# xbowtie1.net
KiCad netlist of a schematic drawn in Altium Designer
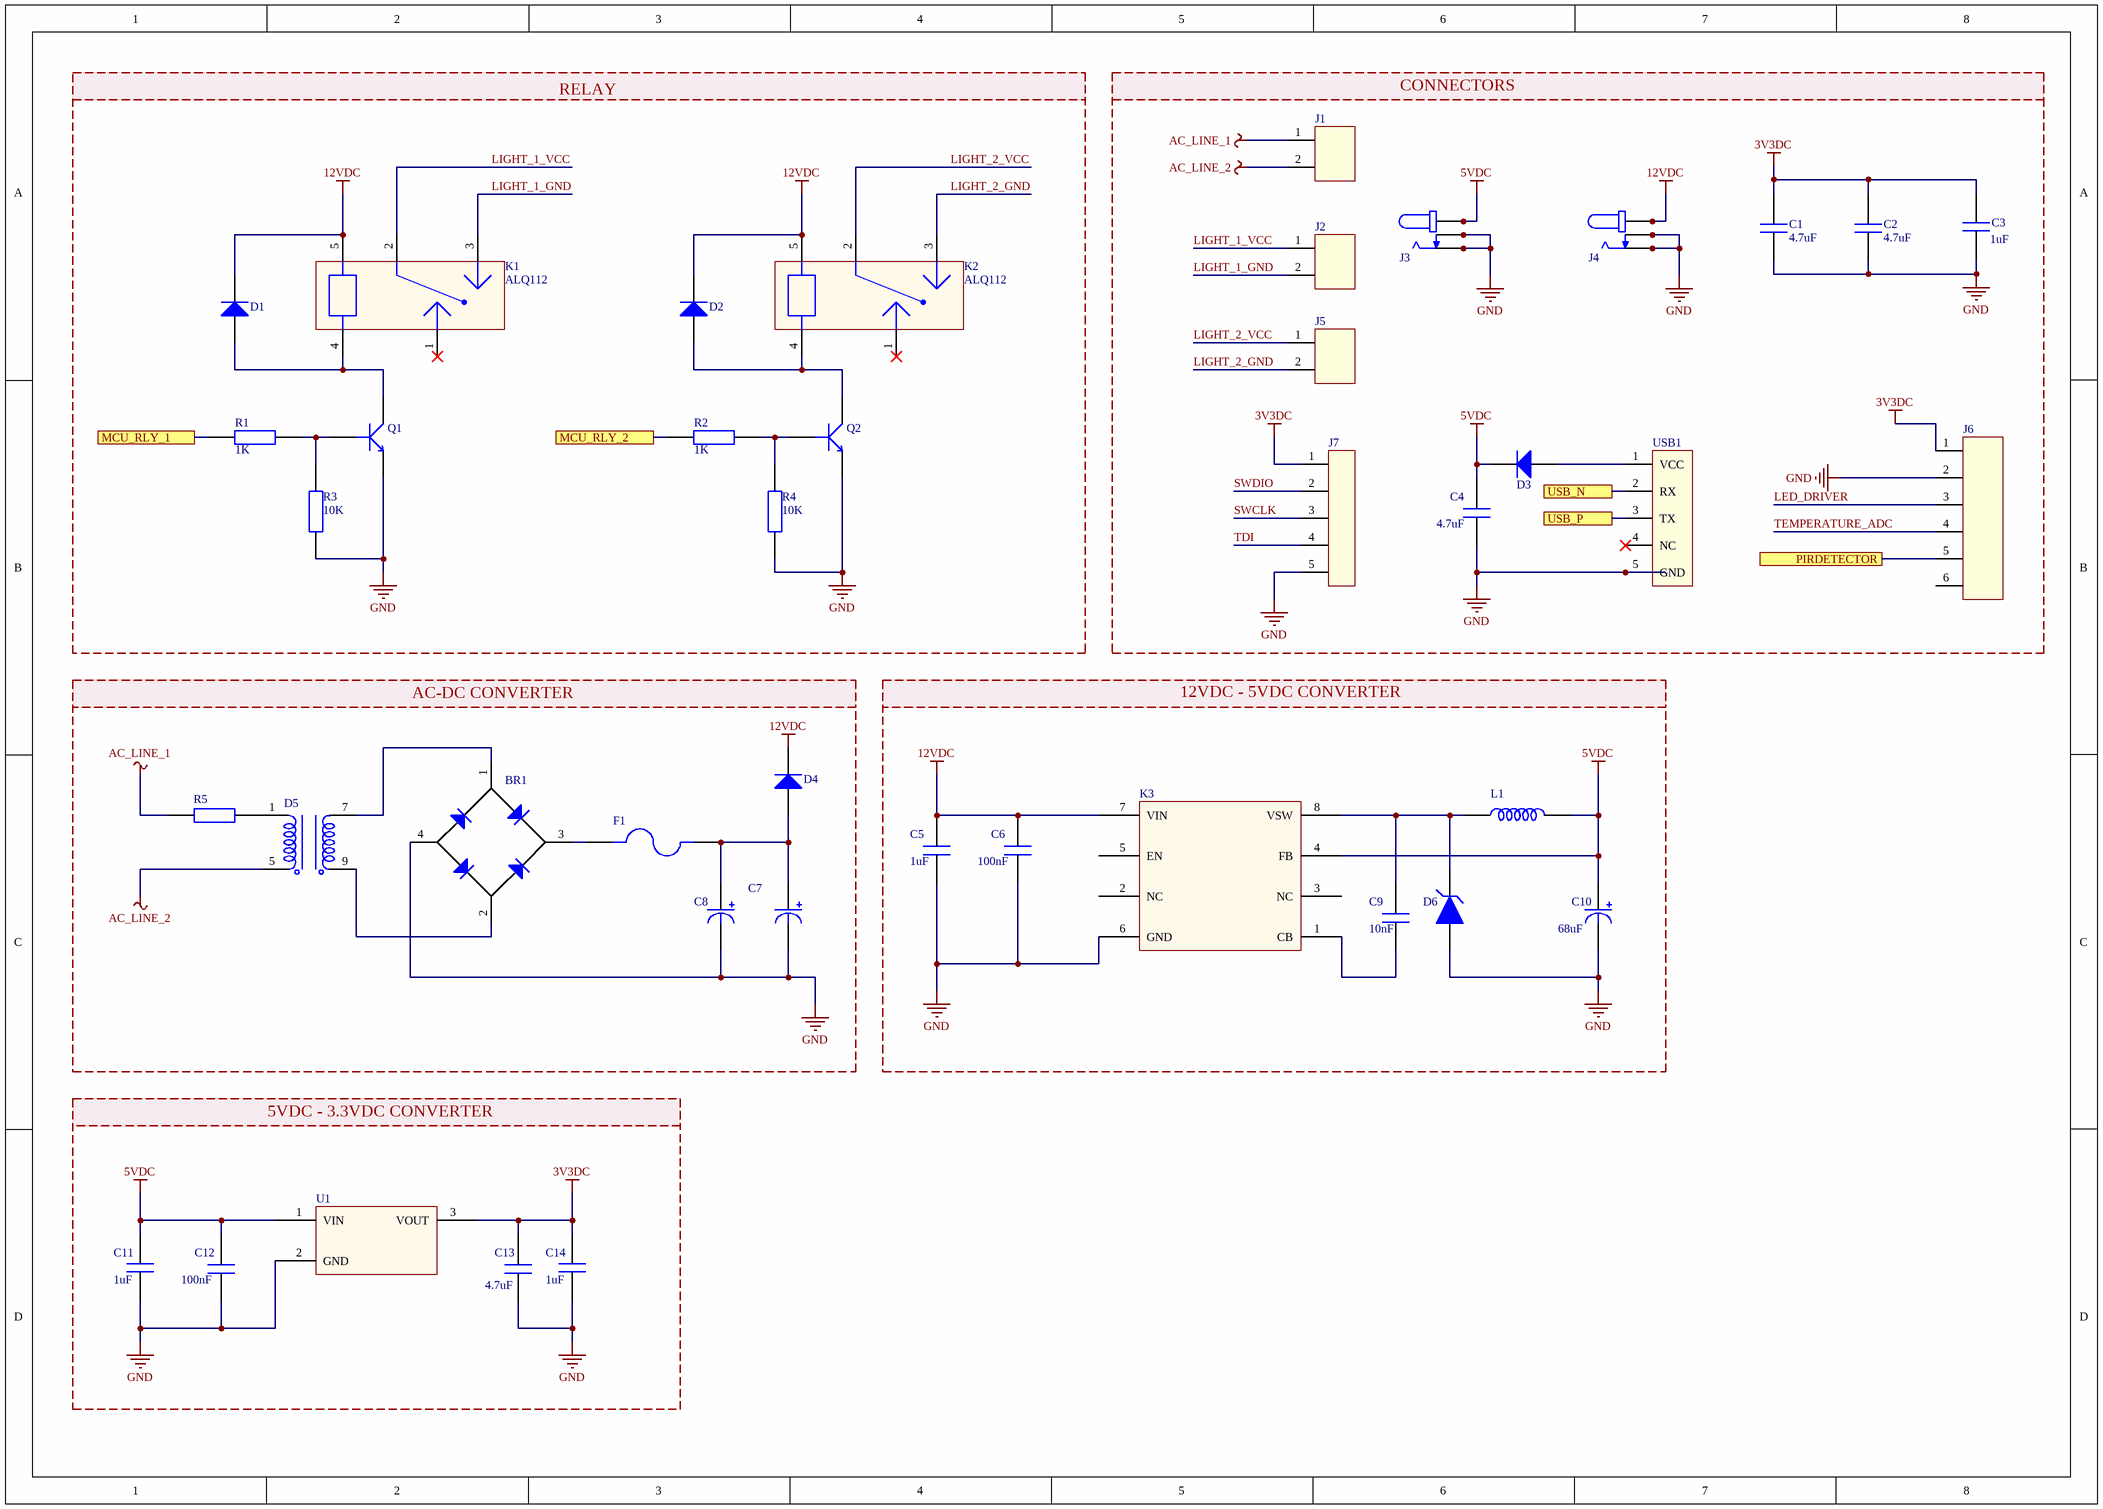
[diagram p0: xbowtie1.SchDoc]

(export (version "E")
  (design (tool "Eeschema 10.0.6"))
  (components
    (comp (ref "BR1") (value "DB105STR") (footprint "DB105STR") (libsource (lib "xbowtie") (part "DB105STR")))
    (comp (ref "C1")
      (value "4.7uF")
      (footprint "CAP_CER 0805")
      (description "CAP CER 4.7uF 0805")
      (fields
        (field (name "MANUFACTURER") "Samsung")
        (field (name "MANUFACTURER PART NUMBER") "CL21A475KBQNNNE")
      )
      (libsource (lib "xbowtie") (part "CAP CER 4.7uF 0805"))
    )
    (comp (ref "C2")
      (value "4.7uF")
      (footprint "CAP_CER 0805")
      (description "CAP CER 4.7uF 0805")
      (fields
        (field (name "MANUFACTURER") "Samsung")
        (field (name "MANUFACTURER PART NUMBER") "CL21A475KBQNNNE")
      )
      (libsource (lib "xbowtie") (part "CAP CER 4.7uF 0805"))
    )
    (comp (ref "C3")
      (value "CAP CER 1uF 0805")
      (footprint "CAP_CER 0805")
      (description "CAP CER 1uF %10 0805")
      (fields
        (field (name "MANUFACTURER") "Samsung")
        (field (name "MANUFACTURER PART NUMBER") "CL21B105KBFNNNE")
        (field (name "CAPACITANCE") "1uF")
      )
      (libsource (lib "xbowtie") (part "CAP CER 1uF 0805"))
    )
    (comp (ref "C4")
      (value "4.7uF")
      (footprint "CAP_CER 0805")
      (description "CAP CER 4.7uF 0805")
      (fields
        (field (name "MANUFACTURER") "Samsung")
        (field (name "MANUFACTURER PART NUMBER") "CL21A475KBQNNNE")
      )
      (libsource (lib "xbowtie") (part "CAP CER 4.7uF 0805"))
    )
    (comp (ref "C5")
      (value "1uF")
      (footprint "CAP_CER 0805")
      (description "CAP CER 1uF %10 0805")
      (fields
        (field (name "MANUFACTURER") "Samsung")
        (field (name "MANUFACTURER PART NUMBER") "CL21B105KBFNNNE")
      )
      (libsource (lib "") (part "CAP CER 1uF 0805_1"))
    )
    (comp (ref "C6")
      (value "100nF")
      (footprint "CAP_CER 0805")
      (libsource (lib "xbowtie") (part "CAP CER 100nF 0805"))
    )
    (comp (ref "C7")
      (value "ESH477M050AH4AA")
      (footprint "ESH477")
      (description "Cap, 470UF, 50V, Alu Elec, Radial")
      (fields (field (name "MANUFACTURER") "KEMET"))
      (libsource (lib "xbowtie") (part "ESH477M050AH4AA"))
    )
    (comp (ref "C8")
      (value "ESH477M050AH4AA")
      (footprint "ESH477")
      (description "Cap, 470UF, 50V, Alu Elec, Radial")
      (fields (field (name "MANUFACTURER") "KEMET"))
      (libsource (lib "xbowtie") (part "ESH477M050AH4AA"))
    )
    (comp (ref "C9")
      (value "10nF")
      (footprint "cap_0603")
      (fields
        (field (name "MANUFACTURER") "Walsin Technologies")
        (field (name "MANUFACTURER PART NUMBER") "0603B103K160CT")
      )
      (libsource (lib "xbowtie") (part "CAP CER 10nF 0603"))
    )
    (comp (ref "C10")
      (value "68uF")
      (footprint "CAP ALU 68 uF")
      (description "Cap Aluminum Lytic 68uF 35V 20%( 6.3 X 7.7mm) SMD 0.34 Ohm 280mA 2000h 105C T/R")
      (fields
        (field (name "MANUFACTURER") "KEMET")
        (field (name "MANUFACTURER PART NUMBER") "EEV686M035A9HAA")
      )
      (libsource (lib "xbowtie") (part "CAP ALU 68 uF"))
    )
    (comp (ref "C11")
      (value "CAP CER 1uF 0805")
      (footprint "CAP_CER 0805")
      (description "CAP CER 1uF %10 0805")
      (fields
        (field (name "MANUFACTURER") "Samsung")
        (field (name "MANUFACTURER PART NUMBER") "CL21B105KBFNNNE")
        (field (name "CAPACITANCE") "1uF")
      )
      (libsource (lib "xbowtie") (part "CAP CER 1uF 0805"))
    )
    (comp (ref "C12")
      (value "100nF")
      (footprint "CAP_CER 0805")
      (libsource (lib "xbowtie") (part "CAP CER 100nF 0805"))
    )
    (comp (ref "C13")
      (value "CAP CER 4.7uF 0805")
      (footprint "CAP_CER 0805")
      (fields
        (field (name "MANUFACTURER") "Samsung")
        (field (name "MANUFACTURER PART NUMBER") "CL21A475KBQNNNE")
        (field (name "TOLERANCE") "10%")
        (field (name "CAPACITANCE") "4.7uF")
      )
      (libsource (lib "xbowtie") (part "CAP CER 4.7uF 0805"))
    )
    (comp (ref "C14")
      (value "CAP CER 1uF 0805")
      (footprint "CAP_CER 0805")
      (description "CAP CER 1uF %10 0805")
      (fields
        (field (name "MANUFACTURER") "Samsung")
        (field (name "MANUFACTURER PART NUMBER") "CL21B105KBFNNNE")
        (field (name "CAPACITANCE") "1uF")
      )
      (libsource (lib "xbowtie") (part "CAP CER 1uF 0805"))
    )
    (comp (ref "D1")
      (value "1N4148WS")
      (footprint "1N4148WS")
      (description "Diode Ultra Fast Recovery Rectifier 75V 0.15A 2-Pin SOD-323F T/R")
      (fields (field (name "MANUFACTURER") "ON Semiconductor / Fairchild"))
      (libsource (lib "xbowtie") (part "1N4148WS"))
    )
    (comp (ref "D2")
      (value "1N4148WS")
      (footprint "1N4148WS")
      (description "Diode Ultra Fast Recovery Rectifier 75V 0.15A 2-Pin SOD-323F T/R")
      (fields (field (name "MANUFACTURER") "ON Semiconductor / Fairchild"))
      (libsource (lib "xbowtie") (part "1N4148WS"))
    )
    (comp (ref "D3")
      (value "1N4148WS")
      (footprint "1N4148WS")
      (description "Diode Ultra Fast Recovery Rectifier 75V 0.15A 2-Pin SOD-323F T/R")
      (fields (field (name "MANUFACTURER") "ON Semiconductor / Fairchild"))
      (libsource (lib "xbowtie") (part "1N4148WS"))
    )
    (comp (ref "D4")
      (value "1N4148WS")
      (footprint "1N4148WS")
      (description "Diode Ultra Fast Recovery Rectifier 75V 0.15A 2-Pin SOD-323F T/R")
      (fields (field (name "MANUFACTURER") "ON Semiconductor / Fairchild"))
      (libsource (lib "xbowtie") (part "1N4148WS"))
    )
    (comp (ref "D5")
      (value "BV302S12010_ZU")
      (footprint "BV302S")
      (libsource (lib "xbowtie") (part "BV302S12010_ZU"))
    )
    (comp (ref "D6")
      (value "1SMB5919BT3G")
      (footprint "1SMB5919BT3G")
      (description "Vz=5.6V 5.32V~5.88V Izt=66.9mA")
      (fields (field (name "MANUFACTURER") "ON Semiconductor"))
      (libsource (lib "xbowtie") (part "1SMB5919BT3G"))
    )
    (comp (ref "F1")
      (value "FUSE 3413.0216.22")
      (footprint "FUSE 3413.0216.22")
      (description "Fuse Chip Fast Acting 1A 32V SMD Solder Pad 1206 Glass T/R VDE/cULus")
      (fields
        (field (name "MANUFACTURER") "Schurter")
        (field (name "MANUFACTURER PART NUMBER") "3413.0216.22")
        (field (name "DESIGNED BY") "Nisanur")
      )
      (libsource (lib "xbowtie") (part "FUSE 3413.0216.22"))
    )
    (comp (ref "J1")
      (value "TBP01R1-508-02BE")
      (footprint "TBP01R1-508")
      (description "2~24 Poles, Pluggable, Receptacle, Horizontal, 5.08 Pitch, Terminal Block Connector")
      (fields (field (name "MANUFACTURER") "CUI Devices"))
      (libsource (lib "xbowtie") (part "TBP01R1-508-02BE"))
    )
    (comp (ref "J2")
      (value "TBP01R1-508-02BE")
      (footprint "TBP01R1-508")
      (description "2~24 Poles, Pluggable, Receptacle, Horizontal, 5.08 Pitch, Terminal Block Connector")
      (fields (field (name "MANUFACTURER") "CUI Devices"))
      (libsource (lib "xbowtie") (part "TBP01R1-508-02BE"))
    )
    (comp (ref "J3")
      (value "PJ-037AH-SMT-TR")
      (footprint "JACK")
      (description "2.0 x 6.3 mm, 5.0 A, Horizontal, Surface Mount (SMT), Dc Power Jack Connector")
      (fields (field (name "MANUFACTURER") "CUI"))
      (libsource (lib "xbowtie") (part "PJ-037AH-SMT-TR"))
    )
    (comp (ref "J4")
      (value "PJ-037AH-SMT-TR")
      (footprint "JACK")
      (description "2.0 x 6.3 mm, 5.0 A, Horizontal, Surface Mount (SMT), Dc Power Jack Connector")
      (fields (field (name "MANUFACTURER") "CUI"))
      (libsource (lib "xbowtie") (part "PJ-037AH-SMT-TR"))
    )
    (comp (ref "J5")
      (value "TBP01R1-508-02BE")
      (footprint "TBP01R1-508")
      (description "2~24 Poles, Pluggable, Receptacle, Horizontal, 5.08 Pitch, Terminal Block Connector")
      (fields (field (name "MANUFACTURER") "CUI Devices"))
      (libsource (lib "xbowtie") (part "TBP01R1-508-02BE"))
    )
    (comp (ref "J6")
      (value "64800611622")
      (footprint "64800611622")
      (description "1.50 mm, 6 pin connector")
      (fields (field (name "MANUFACTURER") "Wurth Electronics"))
      (libsource (lib "xbowtie") (part "64800611622_conn_6pin"))
    )
    (comp (ref "J7")
      (value "SMH-105-02-LS")
      (footprint "5 PIN CONNECTOR")
      (description "Samtec - SMH-105-02-L-S - Receptacle, 2.54MM, Tht, R/a, 5WAY")
      (fields
        (field (name "MANUFACTURER") "Samtec")
        (field (name "MANUFACTURER PART NUMBER") "SMH-105-02-L-S")
      )
      (libsource (lib "xbowtie") (part "SMH-105-02-LS"))
    )
    (comp (ref "K1")
      (value "ALQ112")
      (footprint "ALQ112")
      (description "Electromechanical Relay 12VDC 360Ohm 10(NO)/3(NC)A SPDT (( 20mm 10mm 16mm)) THT Power Relay")
      (fields (field (name "MANUFACTURER") "Panasonic"))
      (libsource (lib "xbowtie") (part "ALQ112"))
    )
    (comp (ref "K2")
      (value "ALQ112")
      (footprint "ALQ112")
      (description "Electromechanical Relay 12VDC 360Ohm 10(NO)/3(NC)A SPDT (( 20mm 10mm 16mm)) THT Power Relay")
      (fields (field (name "MANUFACTURER") "Panasonic"))
      (libsource (lib "xbowtie") (part "ALQ112"))
    )
    (comp (ref "K3")
      (value "LM2675MX-12/NOPB")
      (footprint "LM2675MX-12/NOPB")
      (description "SIMPLE SWITCHER® 6.5V to 40V, 1A Low Component Count Step-Down Regulator 8-SOIC -40 to 125")
      (fields (field (name "MANUFACTURER") "TI National Semiconductor"))
      (libsource (lib "xbowtie") (part "LM2675MX-12/NOPB"))
    )
    (comp (ref "L1")
      (value "78438335470")
      (footprint "IND_1212")
      (description "Power Inductor, Aec-Q200, 47Uh, 0.39A Rohs Compliant: Yes ¦Wurth Elektronik 78438335470")
      (fields (field (name "MANUFACTURER") "Wurth Electronics") (field (name "TOLERANCE") "30%"))
      (libsource (lib "xbowtie") (part "IND 47 uH"))
    )
    (comp (ref "Q1")
      (value "MMBT3904-7-F")
      (footprint "MMBT3904-7-F")
      (description "Transistor General Purpose BJT NPN 40 Volt 0.2A Automotive 3-Pin SOT-23")
      (fields (field (name "MANUFACTURER") "Diodes Zetex"))
      (libsource (lib "xbowtie") (part "MMBT3904-7-F"))
    )
    (comp (ref "Q2")
      (value "MMBT3904-7-F")
      (footprint "MMBT3904-7-F")
      (description "Transistor General Purpose BJT NPN 40 Volt 0.2A Automotive 3-Pin SOT-23")
      (fields (field (name "MANUFACTURER") "Diodes Zetex"))
      (libsource (lib "xbowtie") (part "MMBT3904-7-F"))
    )
    (comp (ref "R1") (value "1K") (footprint "RES_0603") (libsource (lib "xbowtie") (part "RES 1K OHM 0603")))
    (comp (ref "R2") (value "1K") (footprint "RES_0603") (libsource (lib "xbowtie") (part "RES 1K OHM 0603")))
    (comp (ref "R3")
      (value "10K")
      (footprint "RES_0603")
      (description "Res Thin Film 0603 10K Ohm 0.1% 1/10W ±25ppm/°C Molded SMD SMD Punched Carrier T/R")
      (fields
        (field (name "MANUFACTURER") "Panasonic")
        (field (name "MANUFACTURER PART NUMBER") "ERA-3AEB103V")
      )
      (libsource (lib "xbowtie") (part "RES 10K OHM 0603"))
    )
    (comp (ref "R4")
      (value "10K")
      (footprint "RES_0603")
      (description "Res Thin Film 0603 10K Ohm 0.1% 1/10W ±25ppm/°C Molded SMD SMD Punched Carrier T/R")
      (fields
        (field (name "MANUFACTURER") "Panasonic")
        (field (name "MANUFACTURER PART NUMBER") "ERA-3AEB103V")
      )
      (libsource (lib "xbowtie") (part "RES 10K OHM 0603"))
    )
    (comp (ref "R5") (value "5WD27") (footprint "5WD27") (libsource (lib "xbowtie") (part "5WD27")))
    (comp (ref "U1")
      (value "AP7361-33E-13")
      (footprint "AP7361-33E-13")
      (description "AP7361 Series 3.3 V 1 A Low SMT Dropout Fixed-Mode Regulator - SOT-223")
      (fields (field (name "MANUFACTURER") "Diodes"))
      (libsource (lib "xbowtie") (part "AP7361-33E-13"))
    )
    (comp (ref "USB1")
      (value "10118192-0001LF")
      (footprint "MICRO_B_USB")
      (description "CONN USB MICRO B RECPT SMT R/A")
      (fields (field (name "MANUFACTURER") "Amphenol ICC / FCI"))
      (libsource (lib "xbowtie") (part "MİCRO B USB Connector"))
    )
  )
  (nets
    (net (code "1") (name "/LED_DRIVER") (class "Default")
      (node (ref "J6") (pin "3") (pinfunction "TX_3") (pintype "passive"))
    )
    (net (code "2") (name "/LIGHT_1_GND") (class "Default")
      (node (ref "J2") (pin "2") (pinfunction "2_2") (pintype "passive"))
      (node (ref "K1") (pin "3") (pinfunction "4_3") (pintype "passive"))
    )
    (net (code "3") (name "/LIGHT_1_VCC") (class "Default")
      (node (ref "J2") (pin "1") (pinfunction "1_1") (pintype "passive"))
      (node (ref "K1") (pin "2") (pinfunction "3_2") (pintype "passive"))
    )
    (net (code "4") (name "/LIGHT_2_GND") (class "Default")
      (node (ref "J5") (pin "2") (pinfunction "2_2") (pintype "passive"))
      (node (ref "K2") (pin "3") (pinfunction "4_3") (pintype "passive"))
    )
    (net (code "5") (name "/LIGHT_2_VCC") (class "Default")
      (node (ref "J5") (pin "1") (pinfunction "1_1") (pintype "passive"))
      (node (ref "K2") (pin "2") (pinfunction "3_2") (pintype "passive"))
    )
    (net (code "6") (name "/MCU_RLY_1") (class "Default")
      (node (ref "R1") (pin "1") (pinfunction "1_1") (pintype "passive"))
    )
    (net (code "7") (name "/MCU_RLY_2") (class "Default")
      (node (ref "R2") (pin "1") (pinfunction "1_1") (pintype "passive"))
    )
    (net (code "8") (name "/PIRDETECTOR") (class "Default")
      (node (ref "J6") (pin "5") (pinfunction "GND_5") (pintype "passive"))
    )
    (net (code "9") (name "/SWCLK") (class "Default")
      (node (ref "J7") (pin "3") (pinfunction "33_3") (pintype "passive"))
    )
    (net (code "10") (name "/SWDIO") (class "Default")
      (node (ref "J7") (pin "2") (pinfunction "32_2") (pintype "passive"))
    )
    (net (code "11") (name "/TDI") (class "Default")
      (node (ref "J7") (pin "4") (pinfunction "34_4") (pintype "passive"))
    )
    (net (code "12") (name "/TEMPERATURE_ADC") (class "Default")
      (node (ref "J6") (pin "4") (pinfunction "NC_4") (pintype "passive"))
    )
    (net (code "13") (name "/USB_N") (class "Default")
      (node (ref "USB1") (pin "2") (pinfunction "RX_2") (pintype "passive"))
    )
    (net (code "14") (name "/USB_P") (class "Default")
      (node (ref "USB1") (pin "3") (pinfunction "TX_3") (pintype "passive"))
    )
    (net (code "15") (name "3V3DC") (class "Default")
      (node (ref "C1") (pin "2") (pinfunction "2_2") (pintype "passive"))
      (node (ref "C13") (pin "2") (pinfunction "2_2") (pintype "passive"))
      (node (ref "C14") (pin "2") (pinfunction "2_2") (pintype "passive"))
      (node (ref "C2") (pin "2") (pinfunction "2_2") (pintype "passive"))
      (node (ref "C3") (pin "2") (pinfunction "2_2") (pintype "passive"))
      (node (ref "J6") (pin "1") (pinfunction "VCC_1") (pintype "passive"))
      (node (ref "J7") (pin "1") (pinfunction "31_1") (pintype "passive"))
      (node (ref "U1") (pin "3") (pinfunction "VOUT_3") (pintype "passive"))
    )
    (net (code "16") (name "5VDC") (class "Default")
      (node (ref "C10") (pin "1") (pinfunction "1_1") (pintype "passive"))
      (node (ref "C11") (pin "2") (pinfunction "2_2") (pintype "passive"))
      (node (ref "C12") (pin "2") (pinfunction "2_2") (pintype "passive"))
      (node (ref "C4") (pin "2") (pinfunction "2_2") (pintype "passive"))
      (node (ref "D3") (pin "1") (pinfunction "1_1") (pintype "passive"))
      (node (ref "J3") (pin "1A") (pinfunction "1_1A") (pintype "passive"))
      (node (ref "J3") (pin "1B") (pinfunction "1_1B") (pintype "passive"))
      (node (ref "K3") (pin "4") (pinfunction "FB_4") (pintype "passive"))
      (node (ref "L1") (pin "2") (pinfunction "2_2") (pintype "passive"))
      (node (ref "U1") (pin "1") (pinfunction "VIN_1") (pintype "passive"))
    )
    (net (code "17") (name "12VDC") (class "Default")
      (node (ref "C5") (pin "2") (pinfunction "2_2") (pintype "passive"))
      (node (ref "C6") (pin "2") (pinfunction "2_2") (pintype "passive"))
      (node (ref "D1") (pin "1") (pinfunction "1_1") (pintype "passive"))
      (node (ref "D2") (pin "1") (pinfunction "1_1") (pintype "passive"))
      (node (ref "D4") (pin "1") (pinfunction "1_1") (pintype "passive"))
      (node (ref "J4") (pin "1A") (pinfunction "1_1A") (pintype "passive"))
      (node (ref "J4") (pin "1B") (pinfunction "1_1B") (pintype "passive"))
      (node (ref "K1") (pin "5") (pinfunction "6_5") (pintype "passive"))
      (node (ref "K2") (pin "5") (pinfunction "6_5") (pintype "passive"))
      (node (ref "K3") (pin "7") (pinfunction "VIN_7") (pintype "passive"))
    )
    (net (code "18") (name "AC_LINE_1") (class "Default")
      (node (ref "J1") (pin "1") (pinfunction "1_1") (pintype "passive"))
      (node (ref "R5") (pin "1") (pinfunction "1_1") (pintype "passive"))
    )
    (net (code "19") (name "AC_LINE_2") (class "Default")
      (node (ref "D5") (pin "5") (pinfunction "11_5") (pintype "passive"))
      (node (ref "J1") (pin "2") (pinfunction "2_2") (pintype "passive"))
    )
    (net (code "20") (name "GND") (class "Default")
      (node (ref "BR1") (pin "4") (pinfunction "4_4") (pintype "passive"))
      (node (ref "C1") (pin "1") (pinfunction "1_1") (pintype "passive"))
      (node (ref "C10") (pin "2") (pinfunction "2_2") (pintype "passive"))
      (node (ref "C11") (pin "1") (pinfunction "1_1") (pintype "passive"))
      (node (ref "C12") (pin "1") (pinfunction "1_1") (pintype "passive"))
      (node (ref "C13") (pin "1") (pinfunction "1_1") (pintype "passive"))
      (node (ref "C14") (pin "1") (pinfunction "1_1") (pintype "passive"))
      (node (ref "C2") (pin "1") (pinfunction "1_1") (pintype "passive"))
      (node (ref "C3") (pin "1") (pinfunction "1_1") (pintype "passive"))
      (node (ref "C4") (pin "1") (pinfunction "1_1") (pintype "passive"))
      (node (ref "C5") (pin "1") (pinfunction "1_1") (pintype "passive"))
      (node (ref "C6") (pin "1") (pinfunction "1_1") (pintype "passive"))
      (node (ref "C7") (pin "2") (pinfunction "2_2") (pintype "passive"))
      (node (ref "C8") (pin "2") (pinfunction "2_2") (pintype "passive"))
      (node (ref "D6") (pin "1") (pinfunction "1_1") (pintype "passive"))
      (node (ref "J3") (pin "2A") (pinfunction "2_2A") (pintype "passive"))
      (node (ref "J3") (pin "2B") (pinfunction "2_2B") (pintype "passive"))
      (node (ref "J3") (pin "3A") (pinfunction "3_3A") (pintype "passive"))
      (node (ref "J3") (pin "3B") (pinfunction "3_3B") (pintype "passive"))
      (node (ref "J4") (pin "2A") (pinfunction "2_2A") (pintype "passive"))
      (node (ref "J4") (pin "2B") (pinfunction "2_2B") (pintype "passive"))
      (node (ref "J4") (pin "3A") (pinfunction "3_3A") (pintype "passive"))
      (node (ref "J4") (pin "3B") (pinfunction "3_3B") (pintype "passive"))
      (node (ref "J6") (pin "2") (pinfunction "RX_2") (pintype "passive"))
      (node (ref "J7") (pin "5") (pinfunction "35_5") (pintype "passive"))
      (node (ref "K3") (pin "6") (pinfunction "GND_6") (pintype "passive"))
      (node (ref "Q1") (pin "2") (pinfunction "E_2") (pintype "passive"))
      (node (ref "Q2") (pin "2") (pinfunction "E_2") (pintype "passive"))
      (node (ref "R3") (pin "1") (pinfunction "1_1") (pintype "passive"))
      (node (ref "R4") (pin "1") (pinfunction "1_1") (pintype "passive"))
      (node (ref "U1") (pin "2") (pinfunction "GND_2") (pintype "passive"))
      (node (ref "USB1") (pin "5") (pinfunction "GND_5") (pintype "passive"))
    )
    (net (code "21") (name "Net-(BR1-Pad3)") (class "Default")
      (node (ref "BR1") (pin "3") (pinfunction "3_3") (pintype "passive"))
      (node (ref "F1") (pin "1") (pinfunction "1_1") (pintype "passive"))
    )
    (net (code "22") (name "Net-(C7-Pad1)") (class "Default")
      (node (ref "C7") (pin "1") (pinfunction "1_1") (pintype "passive"))
      (node (ref "C8") (pin "1") (pinfunction "1_1") (pintype "passive"))
      (node (ref "D4") (pin "2") (pinfunction "2_2") (pintype "passive"))
      (node (ref "F1") (pin "2") (pinfunction "2_2") (pintype "passive"))
    )
    (net (code "23") (name "Net-(D5-10)") (class "Default")
      (node (ref "D5") (pin "1") (pinfunction "10_1") (pintype "passive"))
      (node (ref "R5") (pin "2") (pinfunction "2_2") (pintype "passive"))
    )
    (net (code "24") (name "Net-(D5-12)") (class "Default")
      (node (ref "BR1") (pin "1") (pinfunction "1_1") (pintype "passive"))
      (node (ref "D5") (pin "7") (pinfunction "12_7") (pintype "passive"))
    )
    (net (code "25") (name "Net-(D5-13)") (class "Default")
      (node (ref "BR1") (pin "2") (pinfunction "2_2") (pintype "passive"))
      (node (ref "D5") (pin "9") (pinfunction "13_9") (pintype "passive"))
    )
    (net (code "26") (name "Net-(K1-5)") (class "Default")
      (node (ref "D1") (pin "2") (pinfunction "2_2") (pintype "passive"))
      (node (ref "K1") (pin "4") (pinfunction "5_4") (pintype "passive"))
      (node (ref "Q1") (pin "C") (pinfunction "C_C") (pintype "passive"))
    )
    (net (code "27") (name "Net-(K2-5)") (class "Default")
      (node (ref "D2") (pin "2") (pinfunction "2_2") (pintype "passive"))
      (node (ref "K2") (pin "4") (pinfunction "5_4") (pintype "passive"))
      (node (ref "Q2") (pin "C") (pinfunction "C_C") (pintype "passive"))
    )
    (net (code "28") (name "Net-(K3-CB)") (class "Default")
      (node (ref "C9") (pin "1") (pinfunction "1_1") (pintype "passive"))
      (node (ref "K3") (pin "1") (pinfunction "CB_1") (pintype "passive"))
    )
    (net (code "29") (name "Net-(K3-VSW)") (class "Default")
      (node (ref "C9") (pin "2") (pinfunction "2_2") (pintype "passive"))
      (node (ref "D6") (pin "2") (pinfunction "2_2") (pintype "passive"))
      (node (ref "K3") (pin "8") (pinfunction "VSW_8") (pintype "passive"))
      (node (ref "L1") (pin "1") (pinfunction "1_1") (pintype "passive"))
    )
    (net (code "30") (name "Net-(Q1-B)") (class "Default")
      (node (ref "Q1") (pin "1") (pinfunction "B_1") (pintype "passive"))
      (node (ref "R1") (pin "2") (pinfunction "2_2") (pintype "passive"))
      (node (ref "R3") (pin "2") (pinfunction "2_2") (pintype "passive"))
    )
    (net (code "31") (name "Net-(Q2-B)") (class "Default")
      (node (ref "Q2") (pin "1") (pinfunction "B_1") (pintype "passive"))
      (node (ref "R2") (pin "2") (pinfunction "2_2") (pintype "passive"))
      (node (ref "R4") (pin "2") (pinfunction "2_2") (pintype "passive"))
    )
    (net (code "32") (name "Net-(USB1-VCC)") (class "Default")
      (node (ref "D3") (pin "2") (pinfunction "2_2") (pintype "passive"))
      (node (ref "USB1") (pin "1") (pinfunction "VCC_1") (pintype "passive"))
    )
    (net (code "33") (name "unconnected-(J6-GND-Pad6)") (class "Default")
      (node (ref "J6") (pin "6") (pinfunction "GND_6") (pintype "passive"))
    )
    (net (code "34") (name "unconnected-(K1-2-Pad1)") (class "Default")
      (node (ref "K1") (pin "1") (pinfunction "2_1") (pintype "passive+no_connect"))
    )
    (net (code "35") (name "unconnected-(K2-2-Pad1)") (class "Default")
      (node (ref "K2") (pin "1") (pinfunction "2_1") (pintype "passive+no_connect"))
    )
    (net (code "36") (name "unconnected-(K3-EN-Pad5)") (class "Default")
      (node (ref "K3") (pin "5") (pinfunction "EN_5") (pintype "passive"))
    )
    (net (code "37") (name "unconnected-(K3-NC-Pad2)") (class "Default")
      (node (ref "K3") (pin "2") (pinfunction "NC_2") (pintype "passive"))
    )
    (net (code "38") (name "unconnected-(K3-NC-Pad3)") (class "Default")
      (node (ref "K3") (pin "3") (pinfunction "NC_3") (pintype "passive"))
    )
    (net (code "39") (name "unconnected-(USB1-NC-Pad4)") (class "Default")
      (node (ref "USB1") (pin "4") (pinfunction "NC_4") (pintype "passive+no_connect"))
    )
  )
)
